# input_signal_conditioning.net
KiCad netlist of a schematic drawn in Altium Designer
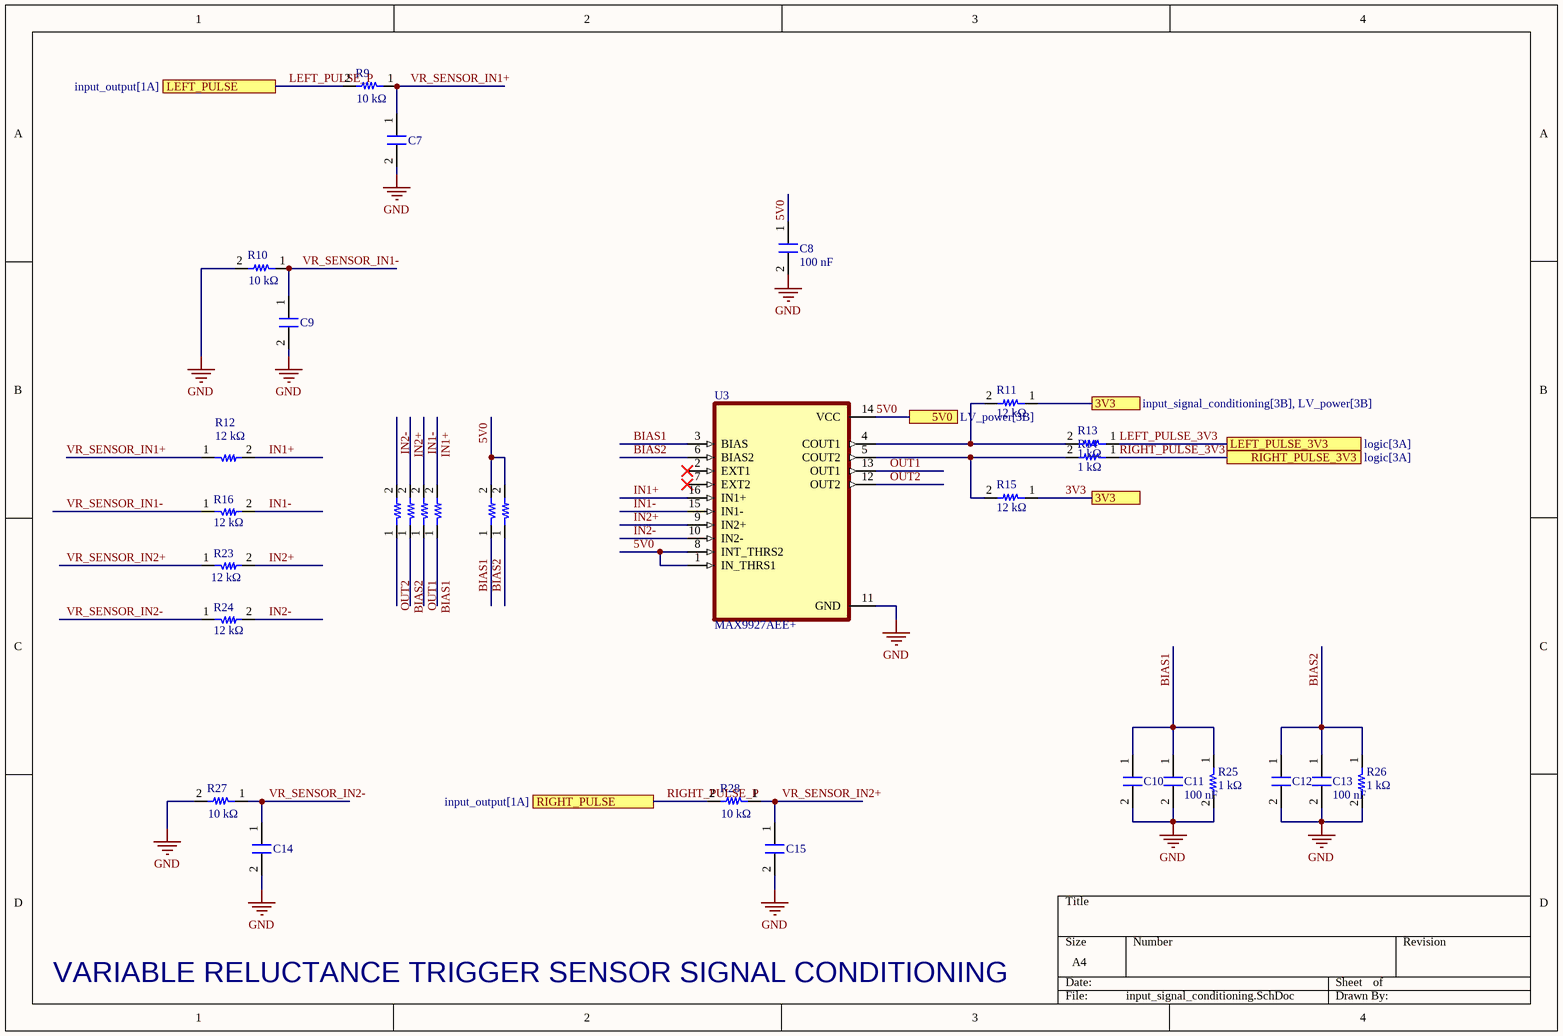
[diagram p0: input_signal_conditioning.SchDoc]

(export (version "E")
  (design (tool "Eeschema 10.0.6"))
  (components
    (comp (ref "C7")
      (value "Capacitor_0402")
      (footprint "0402_fp")
      (libsource (lib "RC_sch") (part "Capacitor_0402"))
    )
    (comp (ref "C8")
      (value "100 nF")
      (footprint "0402_fp")
      (fields (field (name "Comment") "Capacitor_0402"))
      (libsource (lib "RC_sch") (part "Capacitor_0402"))
    )
    (comp (ref "C9")
      (value "Capacitor_0402")
      (footprint "0402_fp")
      (libsource (lib "RC_sch") (part "Capacitor_0402"))
    )
    (comp (ref "C10")
      (value "Capacitor_0603")
      (footprint "0603_FP")
      (libsource (lib "RC_sch") (part "Capacitor_0603"))
    )
    (comp (ref "C11")
      (value "100 nF")
      (footprint "0402_fp")
      (fields (field (name "Comment") "Capacitor_0402"))
      (libsource (lib "RC_sch") (part "Capacitor_0402"))
    )
    (comp (ref "C12")
      (value "Capacitor_0603")
      (footprint "0603_FP")
      (libsource (lib "RC_sch") (part "Capacitor_0603"))
    )
    (comp (ref "C13")
      (value "100 nF")
      (footprint "0402_fp")
      (fields (field (name "Comment") "Capacitor_0402"))
      (libsource (lib "RC_sch") (part "Capacitor_0402"))
    )
    (comp (ref "C14")
      (value "Capacitor_0402")
      (footprint "0402_fp")
      (libsource (lib "RC_sch") (part "Capacitor_0402"))
    )
    (comp (ref "C15")
      (value "Capacitor_0402")
      (footprint "0402_fp")
      (libsource (lib "RC_sch") (part "Capacitor_0402"))
    )
    (comp (ref "R9")
      (value "10 kΩ")
      (footprint "0402_fp")
      (fields (field (name "Comment") "Resistor_0402"))
      (libsource (lib "RC_sch") (part "Resistor_0402"))
    )
    (comp (ref "R10")
      (value "10 kΩ")
      (footprint "0402_fp")
      (fields (field (name "Comment") "Resistor_0402"))
      (libsource (lib "RC_sch") (part "Resistor_0402"))
    )
    (comp (ref "R11")
      (value "12 kΩ")
      (footprint "0402_fp")
      (fields (field (name "Comment") "Resistor_0402"))
      (libsource (lib "RC_sch") (part "Resistor_0402"))
    )
    (comp (ref "R12")
      (value "12 kΩ")
      (footprint "0402_fp")
      (fields (field (name "Comment") "Resistor_0402"))
      (libsource (lib "RC_sch") (part "Resistor_0402"))
    )
    (comp (ref "R13")
      (value "1 kΩ")
      (footprint "0402_fp")
      (fields (field (name "Comment") "Resistor_0402"))
      (libsource (lib "RC_sch") (part "Resistor_0402"))
    )
    (comp (ref "R14")
      (value "1 kΩ")
      (footprint "0402_fp")
      (fields (field (name "Comment") "Resistor_0402"))
      (libsource (lib "RC_sch") (part "Resistor_0402"))
    )
    (comp (ref "R15")
      (value "12 kΩ")
      (footprint "0402_fp")
      (fields (field (name "Comment") "Resistor_0402"))
      (libsource (lib "RC_sch") (part "Resistor_0402"))
    )
    (comp (ref "R16")
      (value "12 kΩ")
      (footprint "0402_fp")
      (fields (field (name "Comment") "Resistor_0402"))
      (libsource (lib "RC_sch") (part "Resistor_0402"))
    )
    (comp (ref "R17")
      (value "Resistor_0402")
      (footprint "0402_fp")
      (libsource (lib "RC_sch") (part "Resistor_0402"))
    )
    (comp (ref "R18")
      (value "Resistor_0402")
      (footprint "0402_fp")
      (libsource (lib "RC_sch") (part "Resistor_0402"))
    )
    (comp (ref "R19")
      (value "Resistor_0402")
      (footprint "0402_fp")
      (libsource (lib "RC_sch") (part "Resistor_0402"))
    )
    (comp (ref "R20")
      (value "Resistor_0402")
      (footprint "0402_fp")
      (libsource (lib "RC_sch") (part "Resistor_0402"))
    )
    (comp (ref "R21")
      (value "Resistor_0402")
      (footprint "0402_fp")
      (libsource (lib "RC_sch") (part "Resistor_0402"))
    )
    (comp (ref "R22")
      (value "Resistor_0402")
      (footprint "0402_fp")
      (libsource (lib "RC_sch") (part "Resistor_0402"))
    )
    (comp (ref "R23")
      (value "12 kΩ")
      (footprint "0402_fp")
      (fields (field (name "Comment") "Resistor_0402"))
      (libsource (lib "RC_sch") (part "Resistor_0402"))
    )
    (comp (ref "R24")
      (value "12 kΩ")
      (footprint "0402_fp")
      (fields (field (name "Comment") "Resistor_0402"))
      (libsource (lib "RC_sch") (part "Resistor_0402"))
    )
    (comp (ref "R25")
      (value "1 kΩ")
      (footprint "0402_fp")
      (fields (field (name "Comment") "Resistor_0402"))
      (libsource (lib "RC_sch") (part "Resistor_0402"))
    )
    (comp (ref "R26")
      (value "1 kΩ")
      (footprint "0402_fp")
      (fields (field (name "Comment") "Resistor_0402"))
      (libsource (lib "RC_sch") (part "Resistor_0402"))
    )
    (comp (ref "R27")
      (value "10 kΩ")
      (footprint "0402_fp")
      (fields (field (name "Comment") "Resistor_0402"))
      (libsource (lib "RC_sch") (part "Resistor_0402"))
    )
    (comp (ref "R28")
      (value "10 kΩ")
      (footprint "0402_fp")
      (fields (field (name "Comment") "Resistor_0402"))
      (libsource (lib "RC_sch") (part "Resistor_0402"))
    )
    (comp (ref "U3")
      (value "MAX9927AEE+")
      (footprint "SOP63P602X175-16N")
      (description "Variable-Reluctance Sensor Interface with Differential Input and Adaptive Peak Threshold")
      (fields (field (name "MF") "Analog Devices"))
      (libsource (lib "MAX9927AEE+") (part "MAX9927AEE+"))
    )
  )
  (nets
    (net (code "1") (name "/3V3") (class "Default")
      (node (ref "R11") (pin "1") (pinfunction "1_1") (pintype "passive"))
      (node (ref "R15") (pin "1") (pinfunction "1_1") (pintype "passive"))
    )
    (net (code "2") (name "/5V0") (class "Default")
      (node (ref "C8") (pin "1") (pinfunction "1_1") (pintype "passive"))
      (node (ref "R21") (pin "2") (pinfunction "2_2") (pintype "passive"))
      (node (ref "R22") (pin "2") (pinfunction "2_2") (pintype "passive"))
      (node (ref "U3") (pin "1") (pinfunction "IN_THRS1_1") (pintype "input"))
      (node (ref "U3") (pin "14") (pinfunction "VCC_14") (pintype "power_in"))
      (node (ref "U3") (pin "8") (pinfunction "INT_THRS2_8") (pintype "input"))
    )
    (net (code "3") (name "/BIAS1") (class "Default")
      (node (ref "C10") (pin "1") (pinfunction "1_1") (pintype "passive"))
      (node (ref "C11") (pin "1") (pinfunction "1_1") (pintype "passive"))
      (node (ref "R20") (pin "1") (pinfunction "1_1") (pintype "passive"))
      (node (ref "R21") (pin "1") (pinfunction "1_1") (pintype "passive"))
      (node (ref "R25") (pin "1") (pinfunction "1_1") (pintype "passive"))
      (node (ref "U3") (pin "3") (pinfunction "BIAS_3") (pintype "input"))
    )
    (net (code "4") (name "/BIAS2") (class "Default")
      (node (ref "C12") (pin "1") (pinfunction "1_1") (pintype "passive"))
      (node (ref "C13") (pin "1") (pinfunction "1_1") (pintype "passive"))
      (node (ref "R18") (pin "1") (pinfunction "1_1") (pintype "passive"))
      (node (ref "R22") (pin "1") (pinfunction "1_1") (pintype "passive"))
      (node (ref "R26") (pin "1") (pinfunction "1_1") (pintype "passive"))
      (node (ref "U3") (pin "6") (pinfunction "BIAS2_6") (pintype "input"))
    )
    (net (code "5") (name "/IN1+") (class "Default")
      (node (ref "R12") (pin "2") (pinfunction "2_2") (pintype "passive"))
      (node (ref "R20") (pin "2") (pinfunction "2_2") (pintype "passive"))
      (node (ref "U3") (pin "16") (pinfunction "IN1+_16") (pintype "input"))
    )
    (net (code "6") (name "/IN1-") (class "Default")
      (node (ref "R16") (pin "2") (pinfunction "2_2") (pintype "passive"))
      (node (ref "R19") (pin "2") (pinfunction "2_2") (pintype "passive"))
      (node (ref "U3") (pin "15") (pinfunction "IN1-_15") (pintype "input"))
    )
    (net (code "7") (name "/IN2+") (class "Default")
      (node (ref "R18") (pin "2") (pinfunction "2_2") (pintype "passive"))
      (node (ref "R23") (pin "2") (pinfunction "2_2") (pintype "passive"))
      (node (ref "U3") (pin "9") (pinfunction "IN2+_9") (pintype "input"))
    )
    (net (code "8") (name "/IN2-") (class "Default")
      (node (ref "R17") (pin "2") (pinfunction "2_2") (pintype "passive"))
      (node (ref "R24") (pin "2") (pinfunction "2_2") (pintype "passive"))
      (node (ref "U3") (pin "10") (pinfunction "IN2-_10") (pintype "input"))
    )
    (net (code "9") (name "/LEFT_PULSE_3V3") (class "Default")
      (node (ref "R13") (pin "1") (pinfunction "1_1") (pintype "passive"))
    )
    (net (code "10") (name "/LEFT_PULSE_P") (class "Default")
      (node (ref "R9") (pin "2") (pinfunction "2_2") (pintype "passive"))
    )
    (net (code "11") (name "/OUT1") (class "Default")
      (node (ref "R19") (pin "1") (pinfunction "1_1") (pintype "passive"))
      (node (ref "U3") (pin "13") (pinfunction "OUT1_13") (pintype "output"))
    )
    (net (code "12") (name "/OUT2") (class "Default")
      (node (ref "R17") (pin "1") (pinfunction "1_1") (pintype "passive"))
      (node (ref "U3") (pin "12") (pinfunction "OUT2_12") (pintype "output"))
    )
    (net (code "13") (name "/RIGHT_PULSE_3V3") (class "Default")
      (node (ref "R14") (pin "1") (pinfunction "1_1") (pintype "passive"))
    )
    (net (code "14") (name "/RIGHT_PULSE_P") (class "Default")
      (node (ref "R28") (pin "2") (pinfunction "2_2") (pintype "passive"))
    )
    (net (code "15") (name "/VR_SENSOR_IN1+") (class "Default")
      (node (ref "C7") (pin "1") (pinfunction "1_1") (pintype "passive"))
      (node (ref "R12") (pin "1") (pinfunction "1_1") (pintype "passive"))
      (node (ref "R9") (pin "1") (pinfunction "1_1") (pintype "passive"))
    )
    (net (code "16") (name "/VR_SENSOR_IN1-") (class "Default")
      (node (ref "C9") (pin "1") (pinfunction "1_1") (pintype "passive"))
      (node (ref "R10") (pin "1") (pinfunction "1_1") (pintype "passive"))
      (node (ref "R16") (pin "1") (pinfunction "1_1") (pintype "passive"))
    )
    (net (code "17") (name "/VR_SENSOR_IN2+") (class "Default")
      (node (ref "C15") (pin "1") (pinfunction "1_1") (pintype "passive"))
      (node (ref "R23") (pin "1") (pinfunction "1_1") (pintype "passive"))
      (node (ref "R28") (pin "1") (pinfunction "1_1") (pintype "passive"))
    )
    (net (code "18") (name "/VR_SENSOR_IN2-") (class "Default")
      (node (ref "C14") (pin "1") (pinfunction "1_1") (pintype "passive"))
      (node (ref "R24") (pin "1") (pinfunction "1_1") (pintype "passive"))
      (node (ref "R27") (pin "1") (pinfunction "1_1") (pintype "passive"))
    )
    (net (code "19") (name "GND") (class "Default")
      (node (ref "C10") (pin "2") (pinfunction "2_2") (pintype "passive"))
      (node (ref "C11") (pin "2") (pinfunction "2_2") (pintype "passive"))
      (node (ref "C12") (pin "2") (pinfunction "2_2") (pintype "passive"))
      (node (ref "C13") (pin "2") (pinfunction "2_2") (pintype "passive"))
      (node (ref "C14") (pin "2") (pinfunction "2_2") (pintype "passive"))
      (node (ref "C15") (pin "2") (pinfunction "2_2") (pintype "passive"))
      (node (ref "C7") (pin "2") (pinfunction "2_2") (pintype "passive"))
      (node (ref "C8") (pin "2") (pinfunction "2_2") (pintype "passive"))
      (node (ref "C9") (pin "2") (pinfunction "2_2") (pintype "passive"))
      (node (ref "R10") (pin "2") (pinfunction "2_2") (pintype "passive"))
      (node (ref "R25") (pin "2") (pinfunction "2_2") (pintype "passive"))
      (node (ref "R26") (pin "2") (pinfunction "2_2") (pintype "passive"))
      (node (ref "R27") (pin "2") (pinfunction "2_2") (pintype "passive"))
      (node (ref "U3") (pin "11") (pinfunction "GND_11") (pintype "power_in"))
    )
    (net (code "20") (name "Net-(U3-COUT1)") (class "Default")
      (node (ref "R11") (pin "2") (pinfunction "2_2") (pintype "passive"))
      (node (ref "R13") (pin "2") (pinfunction "2_2") (pintype "passive"))
      (node (ref "U3") (pin "4") (pinfunction "COUT1_4") (pintype "output"))
    )
    (net (code "21") (name "Net-(U3-COUT2)") (class "Default")
      (node (ref "R14") (pin "2") (pinfunction "2_2") (pintype "passive"))
      (node (ref "R15") (pin "2") (pinfunction "2_2") (pintype "passive"))
      (node (ref "U3") (pin "5") (pinfunction "COUT2_5") (pintype "output"))
    )
    (net (code "22") (name "unconnected-(U3-EXT1-Pad2)") (class "Default")
      (node (ref "U3") (pin "2") (pinfunction "EXT1_2") (pintype "input+no_connect"))
    )
    (net (code "23") (name "unconnected-(U3-EXT2-Pad7)") (class "Default")
      (node (ref "U3") (pin "7") (pinfunction "EXT2_7") (pintype "input+no_connect"))
    )
  )
)
